# Metis_2023.net
KiCad netlist of a schematic drawn in Altium Designer
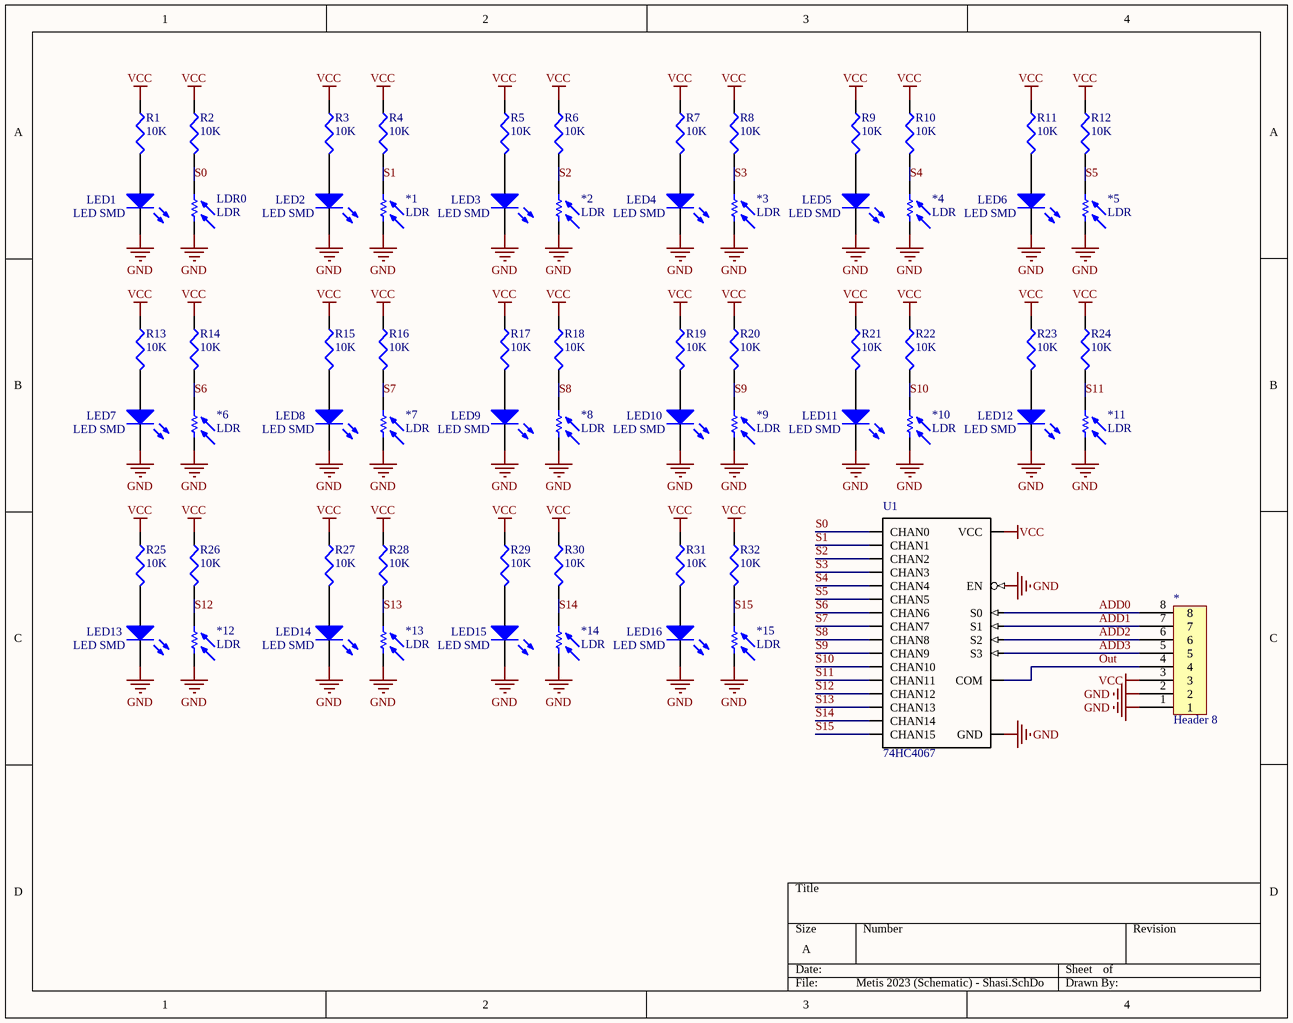
[diagram p0: Metis 2023 (Schematic) - Shasi.SchDoc]

(export (version "E")
  (design (tool "Eeschema 10.0.6"))
  (components
    (comp (ref "*") (value "Header 8") (footprint "HEADER 8") (libsource (lib "Aryalib") (part "Header 8")))
    (comp (ref "*1") (value "LDR") (footprint "LDR") (libsource (lib "Aryalib") (part "LDR")))
    (comp (ref "*2") (value "LDR") (footprint "LDR") (libsource (lib "Aryalib") (part "LDR")))
    (comp (ref "*3") (value "LDR") (footprint "LDR") (libsource (lib "Aryalib") (part "LDR")))
    (comp (ref "*4") (value "LDR") (footprint "LDR") (libsource (lib "Aryalib") (part "LDR")))
    (comp (ref "*5") (value "LDR") (footprint "LDR") (libsource (lib "Aryalib") (part "LDR")))
    (comp (ref "*6") (value "LDR") (footprint "LDR") (libsource (lib "Aryalib") (part "LDR")))
    (comp (ref "*7") (value "LDR") (footprint "LDR") (libsource (lib "Aryalib") (part "LDR")))
    (comp (ref "*8") (value "LDR") (footprint "LDR") (libsource (lib "Aryalib") (part "LDR")))
    (comp (ref "*9") (value "LDR") (footprint "LDR") (libsource (lib "Aryalib") (part "LDR")))
    (comp (ref "*10") (value "LDR") (footprint "LDR") (libsource (lib "Aryalib") (part "LDR")))
    (comp (ref "*11") (value "LDR") (footprint "LDR") (libsource (lib "Aryalib") (part "LDR")))
    (comp (ref "*12") (value "LDR") (footprint "LDR") (libsource (lib "Aryalib") (part "LDR")))
    (comp (ref "*13") (value "LDR") (footprint "LDR") (libsource (lib "Aryalib") (part "LDR")))
    (comp (ref "*14") (value "LDR") (footprint "LDR") (libsource (lib "Aryalib") (part "LDR")))
    (comp (ref "*15") (value "LDR") (footprint "LDR") (libsource (lib "Aryalib") (part "LDR")))
    (comp (ref "LDR0") (value "LDR") (footprint "LDR") (libsource (lib "Aryalib") (part "LDR")))
    (comp (ref "LED1")
      (value "LED SMD")
      (footprint "MY_LED_SMD")
      (libsource (lib "AMINLIB") (part "LED SMD"))
    )
    (comp (ref "LED2")
      (value "LED SMD")
      (footprint "MY_LED_SMD")
      (libsource (lib "AMINLIB") (part "LED SMD"))
    )
    (comp (ref "LED3")
      (value "LED SMD")
      (footprint "MY_LED_SMD")
      (libsource (lib "AMINLIB") (part "LED SMD"))
    )
    (comp (ref "LED4")
      (value "LED SMD")
      (footprint "MY_LED_SMD")
      (libsource (lib "AMINLIB") (part "LED SMD"))
    )
    (comp (ref "LED5")
      (value "LED SMD")
      (footprint "MY_LED_SMD")
      (libsource (lib "AMINLIB") (part "LED SMD"))
    )
    (comp (ref "LED6")
      (value "LED SMD")
      (footprint "MY_LED_SMD")
      (libsource (lib "AMINLIB") (part "LED SMD"))
    )
    (comp (ref "LED7")
      (value "LED SMD")
      (footprint "MY_LED_SMD")
      (libsource (lib "AMINLIB") (part "LED SMD"))
    )
    (comp (ref "LED8")
      (value "LED SMD")
      (footprint "MY_LED_SMD")
      (libsource (lib "AMINLIB") (part "LED SMD"))
    )
    (comp (ref "LED9")
      (value "LED SMD")
      (footprint "MY_LED_SMD")
      (libsource (lib "AMINLIB") (part "LED SMD"))
    )
    (comp (ref "LED10")
      (value "LED SMD")
      (footprint "MY_LED_SMD")
      (libsource (lib "AMINLIB") (part "LED SMD"))
    )
    (comp (ref "LED11")
      (value "LED SMD")
      (footprint "MY_LED_SMD")
      (libsource (lib "AMINLIB") (part "LED SMD"))
    )
    (comp (ref "LED12")
      (value "LED SMD")
      (footprint "MY_LED_SMD")
      (libsource (lib "AMINLIB") (part "LED SMD"))
    )
    (comp (ref "LED13")
      (value "LED SMD")
      (footprint "MY_LED_SMD")
      (libsource (lib "AMINLIB") (part "LED SMD"))
    )
    (comp (ref "LED14")
      (value "LED SMD")
      (footprint "MY_LED_SMD")
      (libsource (lib "AMINLIB") (part "LED SMD"))
    )
    (comp (ref "LED15")
      (value "LED SMD")
      (footprint "MY_LED_SMD")
      (libsource (lib "AMINLIB") (part "LED SMD"))
    )
    (comp (ref "LED16")
      (value "LED SMD")
      (footprint "MY_LED_SMD")
      (libsource (lib "AMINLIB") (part "LED SMD"))
    )
    (comp (ref "R1")
      (value "10K")
      (footprint "MY_RES_SMD_1206")
      (libsource (lib "AMINLIB") (part "RES SMD 1206"))
    )
    (comp (ref "R2")
      (value "10K")
      (footprint "MY_RES_SMD_1206")
      (libsource (lib "AMINLIB") (part "RES SMD 1206"))
    )
    (comp (ref "R3")
      (value "10K")
      (footprint "MY_RES_SMD_1206")
      (libsource (lib "AMINLIB") (part "RES SMD 1206"))
    )
    (comp (ref "R4")
      (value "10K")
      (footprint "MY_RES_SMD_1206")
      (libsource (lib "AMINLIB") (part "RES SMD 1206"))
    )
    (comp (ref "R5")
      (value "10K")
      (footprint "MY_RES_SMD_1206")
      (libsource (lib "AMINLIB") (part "RES SMD 1206"))
    )
    (comp (ref "R6")
      (value "10K")
      (footprint "MY_RES_SMD_1206")
      (libsource (lib "AMINLIB") (part "RES SMD 1206"))
    )
    (comp (ref "R7")
      (value "10K")
      (footprint "MY_RES_SMD_1206")
      (libsource (lib "AMINLIB") (part "RES SMD 1206"))
    )
    (comp (ref "R8")
      (value "10K")
      (footprint "MY_RES_SMD_1206")
      (libsource (lib "AMINLIB") (part "RES SMD 1206"))
    )
    (comp (ref "R9")
      (value "10K")
      (footprint "MY_RES_SMD_1206")
      (libsource (lib "AMINLIB") (part "RES SMD 1206"))
    )
    (comp (ref "R10")
      (value "10K")
      (footprint "MY_RES_SMD_1206")
      (libsource (lib "AMINLIB") (part "RES SMD 1206"))
    )
    (comp (ref "R11")
      (value "10K")
      (footprint "MY_RES_SMD_1206")
      (libsource (lib "AMINLIB") (part "RES SMD 1206"))
    )
    (comp (ref "R12")
      (value "10K")
      (footprint "MY_RES_SMD_1206")
      (libsource (lib "AMINLIB") (part "RES SMD 1206"))
    )
    (comp (ref "R13")
      (value "10K")
      (footprint "MY_RES_SMD_1206")
      (libsource (lib "AMINLIB") (part "RES SMD 1206"))
    )
    (comp (ref "R14")
      (value "10K")
      (footprint "MY_RES_SMD_1206")
      (libsource (lib "AMINLIB") (part "RES SMD 1206"))
    )
    (comp (ref "R15")
      (value "10K")
      (footprint "MY_RES_SMD_1206")
      (libsource (lib "AMINLIB") (part "RES SMD 1206"))
    )
    (comp (ref "R16")
      (value "10K")
      (footprint "MY_RES_SMD_1206")
      (libsource (lib "AMINLIB") (part "RES SMD 1206"))
    )
    (comp (ref "R17")
      (value "10K")
      (footprint "MY_RES_SMD_1206")
      (libsource (lib "AMINLIB") (part "RES SMD 1206"))
    )
    (comp (ref "R18")
      (value "10K")
      (footprint "MY_RES_SMD_1206")
      (libsource (lib "AMINLIB") (part "RES SMD 1206"))
    )
    (comp (ref "R19")
      (value "10K")
      (footprint "MY_RES_SMD_1206")
      (libsource (lib "AMINLIB") (part "RES SMD 1206"))
    )
    (comp (ref "R20")
      (value "10K")
      (footprint "MY_RES_SMD_1206")
      (libsource (lib "AMINLIB") (part "RES SMD 1206"))
    )
    (comp (ref "R21")
      (value "10K")
      (footprint "MY_RES_SMD_1206")
      (libsource (lib "AMINLIB") (part "RES SMD 1206"))
    )
    (comp (ref "R22")
      (value "10K")
      (footprint "MY_RES_SMD_1206")
      (libsource (lib "AMINLIB") (part "RES SMD 1206"))
    )
    (comp (ref "R23")
      (value "10K")
      (footprint "MY_RES_SMD_1206")
      (libsource (lib "AMINLIB") (part "RES SMD 1206"))
    )
    (comp (ref "R24")
      (value "10K")
      (footprint "MY_RES_SMD_1206")
      (libsource (lib "AMINLIB") (part "RES SMD 1206"))
    )
    (comp (ref "R25")
      (value "10K")
      (footprint "MY_RES_SMD_1206")
      (libsource (lib "AMINLIB") (part "RES SMD 1206"))
    )
    (comp (ref "R26")
      (value "10K")
      (footprint "MY_RES_SMD_1206")
      (libsource (lib "AMINLIB") (part "RES SMD 1206"))
    )
    (comp (ref "R27")
      (value "10K")
      (footprint "MY_RES_SMD_1206")
      (libsource (lib "AMINLIB") (part "RES SMD 1206"))
    )
    (comp (ref "R28")
      (value "10K")
      (footprint "MY_RES_SMD_1206")
      (libsource (lib "AMINLIB") (part "RES SMD 1206"))
    )
    (comp (ref "R29")
      (value "10K")
      (footprint "MY_RES_SMD_1206")
      (libsource (lib "AMINLIB") (part "RES SMD 1206"))
    )
    (comp (ref "R30")
      (value "10K")
      (footprint "MY_RES_SMD_1206")
      (libsource (lib "AMINLIB") (part "RES SMD 1206"))
    )
    (comp (ref "R31")
      (value "10K")
      (footprint "MY_RES_SMD_1206")
      (libsource (lib "AMINLIB") (part "RES SMD 1206"))
    )
    (comp (ref "R32")
      (value "10K")
      (footprint "MY_RES_SMD_1206")
      (libsource (lib "AMINLIB") (part "RES SMD 1206"))
    )
    (comp (ref "U1")
      (value "74HC4067")
      (footprint "*SOIC-24_74HC4067(Primary)")
      (description "Analog Switch/Analog Multiplexer Single 16:1 24-Pin SSOP T/R")
      (fields (field (name "MF") "Nexperia"))
      (libsource (lib "74HC4067") (part "74HC4067"))
    )
  )
  (nets
    (net (code "1") (name "/ADD0") (class "Default")
      (node (ref "*") (pin "8") (pinfunction "8_8") (pintype "passive"))
      (node (ref "U1") (pin "P10") (pinfunction "S0_P10") (pintype "input"))
    )
    (net (code "2") (name "/ADD1") (class "Default")
      (node (ref "*") (pin "7") (pinfunction "7_7") (pintype "passive"))
      (node (ref "U1") (pin "P11") (pinfunction "S1_P11") (pintype "input"))
    )
    (net (code "3") (name "/ADD2") (class "Default")
      (node (ref "*") (pin "6") (pinfunction "6_6") (pintype "passive"))
      (node (ref "U1") (pin "P14") (pinfunction "S2_P14") (pintype "input"))
    )
    (net (code "4") (name "/ADD3") (class "Default")
      (node (ref "*") (pin "5") (pinfunction "5_5") (pintype "passive"))
      (node (ref "U1") (pin "P13") (pinfunction "S3_P13") (pintype "input"))
    )
    (net (code "5") (name "/Out") (class "Default")
      (node (ref "*") (pin "4") (pinfunction "4_4") (pintype "passive"))
      (node (ref "U1") (pin "P1") (pinfunction "COM_P1") (pintype "bidirectional"))
    )
    (net (code "6") (name "/S0") (class "Default")
      (node (ref "LDR0") (pin "1") (pinfunction "1_1") (pintype "passive"))
      (node (ref "R2") (pin "2") (pinfunction "2_2") (pintype "passive"))
      (node (ref "U1") (pin "P9") (pinfunction "CHAN0_P9") (pintype "bidirectional"))
    )
    (net (code "7") (name "/S1") (class "Default")
      (node (ref "*1") (pin "1") (pinfunction "1_1") (pintype "passive"))
      (node (ref "R4") (pin "2") (pinfunction "2_2") (pintype "passive"))
      (node (ref "U1") (pin "P8") (pinfunction "CHAN1_P8") (pintype "bidirectional"))
    )
    (net (code "8") (name "/S2") (class "Default")
      (node (ref "*2") (pin "1") (pinfunction "1_1") (pintype "passive"))
      (node (ref "R6") (pin "2") (pinfunction "2_2") (pintype "passive"))
      (node (ref "U1") (pin "P7") (pinfunction "CHAN2_P7") (pintype "bidirectional"))
    )
    (net (code "9") (name "/S3") (class "Default")
      (node (ref "*3") (pin "1") (pinfunction "1_1") (pintype "passive"))
      (node (ref "R8") (pin "2") (pinfunction "2_2") (pintype "passive"))
      (node (ref "U1") (pin "P6") (pinfunction "CHAN3_P6") (pintype "bidirectional"))
    )
    (net (code "10") (name "/S4") (class "Default")
      (node (ref "*4") (pin "1") (pinfunction "1_1") (pintype "passive"))
      (node (ref "R10") (pin "2") (pinfunction "2_2") (pintype "passive"))
      (node (ref "U1") (pin "P5") (pinfunction "CHAN4_P5") (pintype "bidirectional"))
    )
    (net (code "11") (name "/S5") (class "Default")
      (node (ref "*5") (pin "1") (pinfunction "1_1") (pintype "passive"))
      (node (ref "R12") (pin "2") (pinfunction "2_2") (pintype "passive"))
      (node (ref "U1") (pin "P4") (pinfunction "CHAN5_P4") (pintype "bidirectional"))
    )
    (net (code "12") (name "/S6") (class "Default")
      (node (ref "*6") (pin "1") (pinfunction "1_1") (pintype "passive"))
      (node (ref "R14") (pin "2") (pinfunction "2_2") (pintype "passive"))
      (node (ref "U1") (pin "P3") (pinfunction "CHAN6_P3") (pintype "bidirectional"))
    )
    (net (code "13") (name "/S7") (class "Default")
      (node (ref "*7") (pin "1") (pinfunction "1_1") (pintype "passive"))
      (node (ref "R16") (pin "2") (pinfunction "2_2") (pintype "passive"))
      (node (ref "U1") (pin "P2") (pinfunction "CHAN7_P2") (pintype "bidirectional"))
    )
    (net (code "14") (name "/S8") (class "Default")
      (node (ref "*8") (pin "1") (pinfunction "1_1") (pintype "passive"))
      (node (ref "R18") (pin "2") (pinfunction "2_2") (pintype "passive"))
      (node (ref "U1") (pin "P23") (pinfunction "CHAN8_P23") (pintype "bidirectional"))
    )
    (net (code "15") (name "/S9") (class "Default")
      (node (ref "*9") (pin "1") (pinfunction "1_1") (pintype "passive"))
      (node (ref "R20") (pin "2") (pinfunction "2_2") (pintype "passive"))
      (node (ref "U1") (pin "P22") (pinfunction "CHAN9_P22") (pintype "bidirectional"))
    )
    (net (code "16") (name "/S10") (class "Default")
      (node (ref "*10") (pin "1") (pinfunction "1_1") (pintype "passive"))
      (node (ref "R22") (pin "2") (pinfunction "2_2") (pintype "passive"))
      (node (ref "U1") (pin "P21") (pinfunction "CHAN10_P21") (pintype "bidirectional"))
    )
    (net (code "17") (name "/S11") (class "Default")
      (node (ref "*11") (pin "1") (pinfunction "1_1") (pintype "passive"))
      (node (ref "R24") (pin "2") (pinfunction "2_2") (pintype "passive"))
      (node (ref "U1") (pin "P20") (pinfunction "CHAN11_P20") (pintype "bidirectional"))
    )
    (net (code "18") (name "/S12") (class "Default")
      (node (ref "*12") (pin "1") (pinfunction "1_1") (pintype "passive"))
      (node (ref "R26") (pin "2") (pinfunction "2_2") (pintype "passive"))
      (node (ref "U1") (pin "P19") (pinfunction "CHAN12_P19") (pintype "bidirectional"))
    )
    (net (code "19") (name "/S13") (class "Default")
      (node (ref "*13") (pin "1") (pinfunction "1_1") (pintype "passive"))
      (node (ref "R28") (pin "2") (pinfunction "2_2") (pintype "passive"))
      (node (ref "U1") (pin "P18") (pinfunction "CHAN13_P18") (pintype "bidirectional"))
    )
    (net (code "20") (name "/S14") (class "Default")
      (node (ref "*14") (pin "1") (pinfunction "1_1") (pintype "passive"))
      (node (ref "R30") (pin "2") (pinfunction "2_2") (pintype "passive"))
      (node (ref "U1") (pin "P17") (pinfunction "CHAN14_P17") (pintype "bidirectional"))
    )
    (net (code "21") (name "/S15") (class "Default")
      (node (ref "*15") (pin "1") (pinfunction "1_1") (pintype "passive"))
      (node (ref "R32") (pin "2") (pinfunction "2_2") (pintype "passive"))
      (node (ref "U1") (pin "P16") (pinfunction "CHAN15_P16") (pintype "bidirectional"))
    )
    (net (code "22") (name "GND") (class "Default")
      (node (ref "*") (pin "1") (pinfunction "1_1") (pintype "passive"))
      (node (ref "*") (pin "2") (pinfunction "2_2") (pintype "passive"))
      (node (ref "*1") (pin "2") (pinfunction "2_2") (pintype "passive"))
      (node (ref "*10") (pin "2") (pinfunction "2_2") (pintype "passive"))
      (node (ref "*11") (pin "2") (pinfunction "2_2") (pintype "passive"))
      (node (ref "*12") (pin "2") (pinfunction "2_2") (pintype "passive"))
      (node (ref "*13") (pin "2") (pinfunction "2_2") (pintype "passive"))
      (node (ref "*14") (pin "2") (pinfunction "2_2") (pintype "passive"))
      (node (ref "*15") (pin "2") (pinfunction "2_2") (pintype "passive"))
      (node (ref "*2") (pin "2") (pinfunction "2_2") (pintype "passive"))
      (node (ref "*3") (pin "2") (pinfunction "2_2") (pintype "passive"))
      (node (ref "*4") (pin "2") (pinfunction "2_2") (pintype "passive"))
      (node (ref "*5") (pin "2") (pinfunction "2_2") (pintype "passive"))
      (node (ref "*6") (pin "2") (pinfunction "2_2") (pintype "passive"))
      (node (ref "*7") (pin "2") (pinfunction "2_2") (pintype "passive"))
      (node (ref "*8") (pin "2") (pinfunction "2_2") (pintype "passive"))
      (node (ref "*9") (pin "2") (pinfunction "2_2") (pintype "passive"))
      (node (ref "LDR0") (pin "2") (pinfunction "2_2") (pintype "passive"))
      (node (ref "LED1") (pin "2") (pinfunction "K_2") (pintype "passive"))
      (node (ref "LED10") (pin "2") (pinfunction "K_2") (pintype "passive"))
      (node (ref "LED11") (pin "2") (pinfunction "K_2") (pintype "passive"))
      (node (ref "LED12") (pin "2") (pinfunction "K_2") (pintype "passive"))
      (node (ref "LED13") (pin "2") (pinfunction "K_2") (pintype "passive"))
      (node (ref "LED14") (pin "2") (pinfunction "K_2") (pintype "passive"))
      (node (ref "LED15") (pin "2") (pinfunction "K_2") (pintype "passive"))
      (node (ref "LED16") (pin "2") (pinfunction "K_2") (pintype "passive"))
      (node (ref "LED2") (pin "2") (pinfunction "K_2") (pintype "passive"))
      (node (ref "LED3") (pin "2") (pinfunction "K_2") (pintype "passive"))
      (node (ref "LED4") (pin "2") (pinfunction "K_2") (pintype "passive"))
      (node (ref "LED5") (pin "2") (pinfunction "K_2") (pintype "passive"))
      (node (ref "LED6") (pin "2") (pinfunction "K_2") (pintype "passive"))
      (node (ref "LED7") (pin "2") (pinfunction "K_2") (pintype "passive"))
      (node (ref "LED8") (pin "2") (pinfunction "K_2") (pintype "passive"))
      (node (ref "LED9") (pin "2") (pinfunction "K_2") (pintype "passive"))
      (node (ref "U1") (pin "P12") (pinfunction "GND_P12") (pintype "bidirectional"))
      (node (ref "U1") (pin "P15") (pinfunction "EN_P15") (pintype "input"))
    )
    (net (code "23") (name "Net-(LED1-A)") (class "Default")
      (node (ref "LED1") (pin "1") (pinfunction "A_1") (pintype "passive"))
      (node (ref "R1") (pin "2") (pinfunction "2_2") (pintype "passive"))
    )
    (net (code "24") (name "Net-(LED2-A)") (class "Default")
      (node (ref "LED2") (pin "1") (pinfunction "A_1") (pintype "passive"))
      (node (ref "R3") (pin "2") (pinfunction "2_2") (pintype "passive"))
    )
    (net (code "25") (name "Net-(LED3-A)") (class "Default")
      (node (ref "LED3") (pin "1") (pinfunction "A_1") (pintype "passive"))
      (node (ref "R5") (pin "2") (pinfunction "2_2") (pintype "passive"))
    )
    (net (code "26") (name "Net-(LED4-A)") (class "Default")
      (node (ref "LED4") (pin "1") (pinfunction "A_1") (pintype "passive"))
      (node (ref "R7") (pin "2") (pinfunction "2_2") (pintype "passive"))
    )
    (net (code "27") (name "Net-(LED5-A)") (class "Default")
      (node (ref "LED5") (pin "1") (pinfunction "A_1") (pintype "passive"))
      (node (ref "R9") (pin "2") (pinfunction "2_2") (pintype "passive"))
    )
    (net (code "28") (name "Net-(LED6-A)") (class "Default")
      (node (ref "LED6") (pin "1") (pinfunction "A_1") (pintype "passive"))
      (node (ref "R11") (pin "2") (pinfunction "2_2") (pintype "passive"))
    )
    (net (code "29") (name "Net-(LED7-A)") (class "Default")
      (node (ref "LED7") (pin "1") (pinfunction "A_1") (pintype "passive"))
      (node (ref "R13") (pin "2") (pinfunction "2_2") (pintype "passive"))
    )
    (net (code "30") (name "Net-(LED8-A)") (class "Default")
      (node (ref "LED8") (pin "1") (pinfunction "A_1") (pintype "passive"))
      (node (ref "R15") (pin "2") (pinfunction "2_2") (pintype "passive"))
    )
    (net (code "31") (name "Net-(LED9-A)") (class "Default")
      (node (ref "LED9") (pin "1") (pinfunction "A_1") (pintype "passive"))
      (node (ref "R17") (pin "2") (pinfunction "2_2") (pintype "passive"))
    )
    (net (code "32") (name "Net-(LED10-A)") (class "Default")
      (node (ref "LED10") (pin "1") (pinfunction "A_1") (pintype "passive"))
      (node (ref "R19") (pin "2") (pinfunction "2_2") (pintype "passive"))
    )
    (net (code "33") (name "Net-(LED11-A)") (class "Default")
      (node (ref "LED11") (pin "1") (pinfunction "A_1") (pintype "passive"))
      (node (ref "R21") (pin "2") (pinfunction "2_2") (pintype "passive"))
    )
    (net (code "34") (name "Net-(LED12-A)") (class "Default")
      (node (ref "LED12") (pin "1") (pinfunction "A_1") (pintype "passive"))
      (node (ref "R23") (pin "2") (pinfunction "2_2") (pintype "passive"))
    )
    (net (code "35") (name "Net-(LED13-A)") (class "Default")
      (node (ref "LED13") (pin "1") (pinfunction "A_1") (pintype "passive"))
      (node (ref "R25") (pin "2") (pinfunction "2_2") (pintype "passive"))
    )
    (net (code "36") (name "Net-(LED14-A)") (class "Default")
      (node (ref "LED14") (pin "1") (pinfunction "A_1") (pintype "passive"))
      (node (ref "R27") (pin "2") (pinfunction "2_2") (pintype "passive"))
    )
    (net (code "37") (name "Net-(LED15-A)") (class "Default")
      (node (ref "LED15") (pin "1") (pinfunction "A_1") (pintype "passive"))
      (node (ref "R29") (pin "2") (pinfunction "2_2") (pintype "passive"))
    )
    (net (code "38") (name "Net-(LED16-A)") (class "Default")
      (node (ref "LED16") (pin "1") (pinfunction "A_1") (pintype "passive"))
      (node (ref "R31") (pin "2") (pinfunction "2_2") (pintype "passive"))
    )
    (net (code "39") (name "VCC") (class "Default")
      (node (ref "*") (pin "3") (pinfunction "3_3") (pintype "passive"))
      (node (ref "R1") (pin "1") (pinfunction "1_1") (pintype "passive"))
      (node (ref "R10") (pin "1") (pinfunction "1_1") (pintype "passive"))
      (node (ref "R11") (pin "1") (pinfunction "1_1") (pintype "passive"))
      (node (ref "R12") (pin "1") (pinfunction "1_1") (pintype "passive"))
      (node (ref "R13") (pin "1") (pinfunction "1_1") (pintype "passive"))
      (node (ref "R14") (pin "1") (pinfunction "1_1") (pintype "passive"))
      (node (ref "R15") (pin "1") (pinfunction "1_1") (pintype "passive"))
      (node (ref "R16") (pin "1") (pinfunction "1_1") (pintype "passive"))
      (node (ref "R17") (pin "1") (pinfunction "1_1") (pintype "passive"))
      (node (ref "R18") (pin "1") (pinfunction "1_1") (pintype "passive"))
      (node (ref "R19") (pin "1") (pinfunction "1_1") (pintype "passive"))
      (node (ref "R2") (pin "1") (pinfunction "1_1") (pintype "passive"))
      (node (ref "R20") (pin "1") (pinfunction "1_1") (pintype "passive"))
      (node (ref "R21") (pin "1") (pinfunction "1_1") (pintype "passive"))
      (node (ref "R22") (pin "1") (pinfunction "1_1") (pintype "passive"))
      (node (ref "R23") (pin "1") (pinfunction "1_1") (pintype "passive"))
      (node (ref "R24") (pin "1") (pinfunction "1_1") (pintype "passive"))
      (node (ref "R25") (pin "1") (pinfunction "1_1") (pintype "passive"))
      (node (ref "R26") (pin "1") (pinfunction "1_1") (pintype "passive"))
      (node (ref "R27") (pin "1") (pinfunction "1_1") (pintype "passive"))
      (node (ref "R28") (pin "1") (pinfunction "1_1") (pintype "passive"))
      (node (ref "R29") (pin "1") (pinfunction "1_1") (pintype "passive"))
      (node (ref "R3") (pin "1") (pinfunction "1_1") (pintype "passive"))
      (node (ref "R30") (pin "1") (pinfunction "1_1") (pintype "passive"))
      (node (ref "R31") (pin "1") (pinfunction "1_1") (pintype "passive"))
      (node (ref "R32") (pin "1") (pinfunction "1_1") (pintype "passive"))
      (node (ref "R4") (pin "1") (pinfunction "1_1") (pintype "passive"))
      (node (ref "R5") (pin "1") (pinfunction "1_1") (pintype "passive"))
      (node (ref "R6") (pin "1") (pinfunction "1_1") (pintype "passive"))
      (node (ref "R7") (pin "1") (pinfunction "1_1") (pintype "passive"))
      (node (ref "R8") (pin "1") (pinfunction "1_1") (pintype "passive"))
      (node (ref "R9") (pin "1") (pinfunction "1_1") (pintype "passive"))
      (node (ref "U1") (pin "P24") (pinfunction "VCC_P24") (pintype "bidirectional"))
    )
  )
)
